# HABSat2_schematic1502.net
KiCad netlist of a schematic drawn in EasyEDA
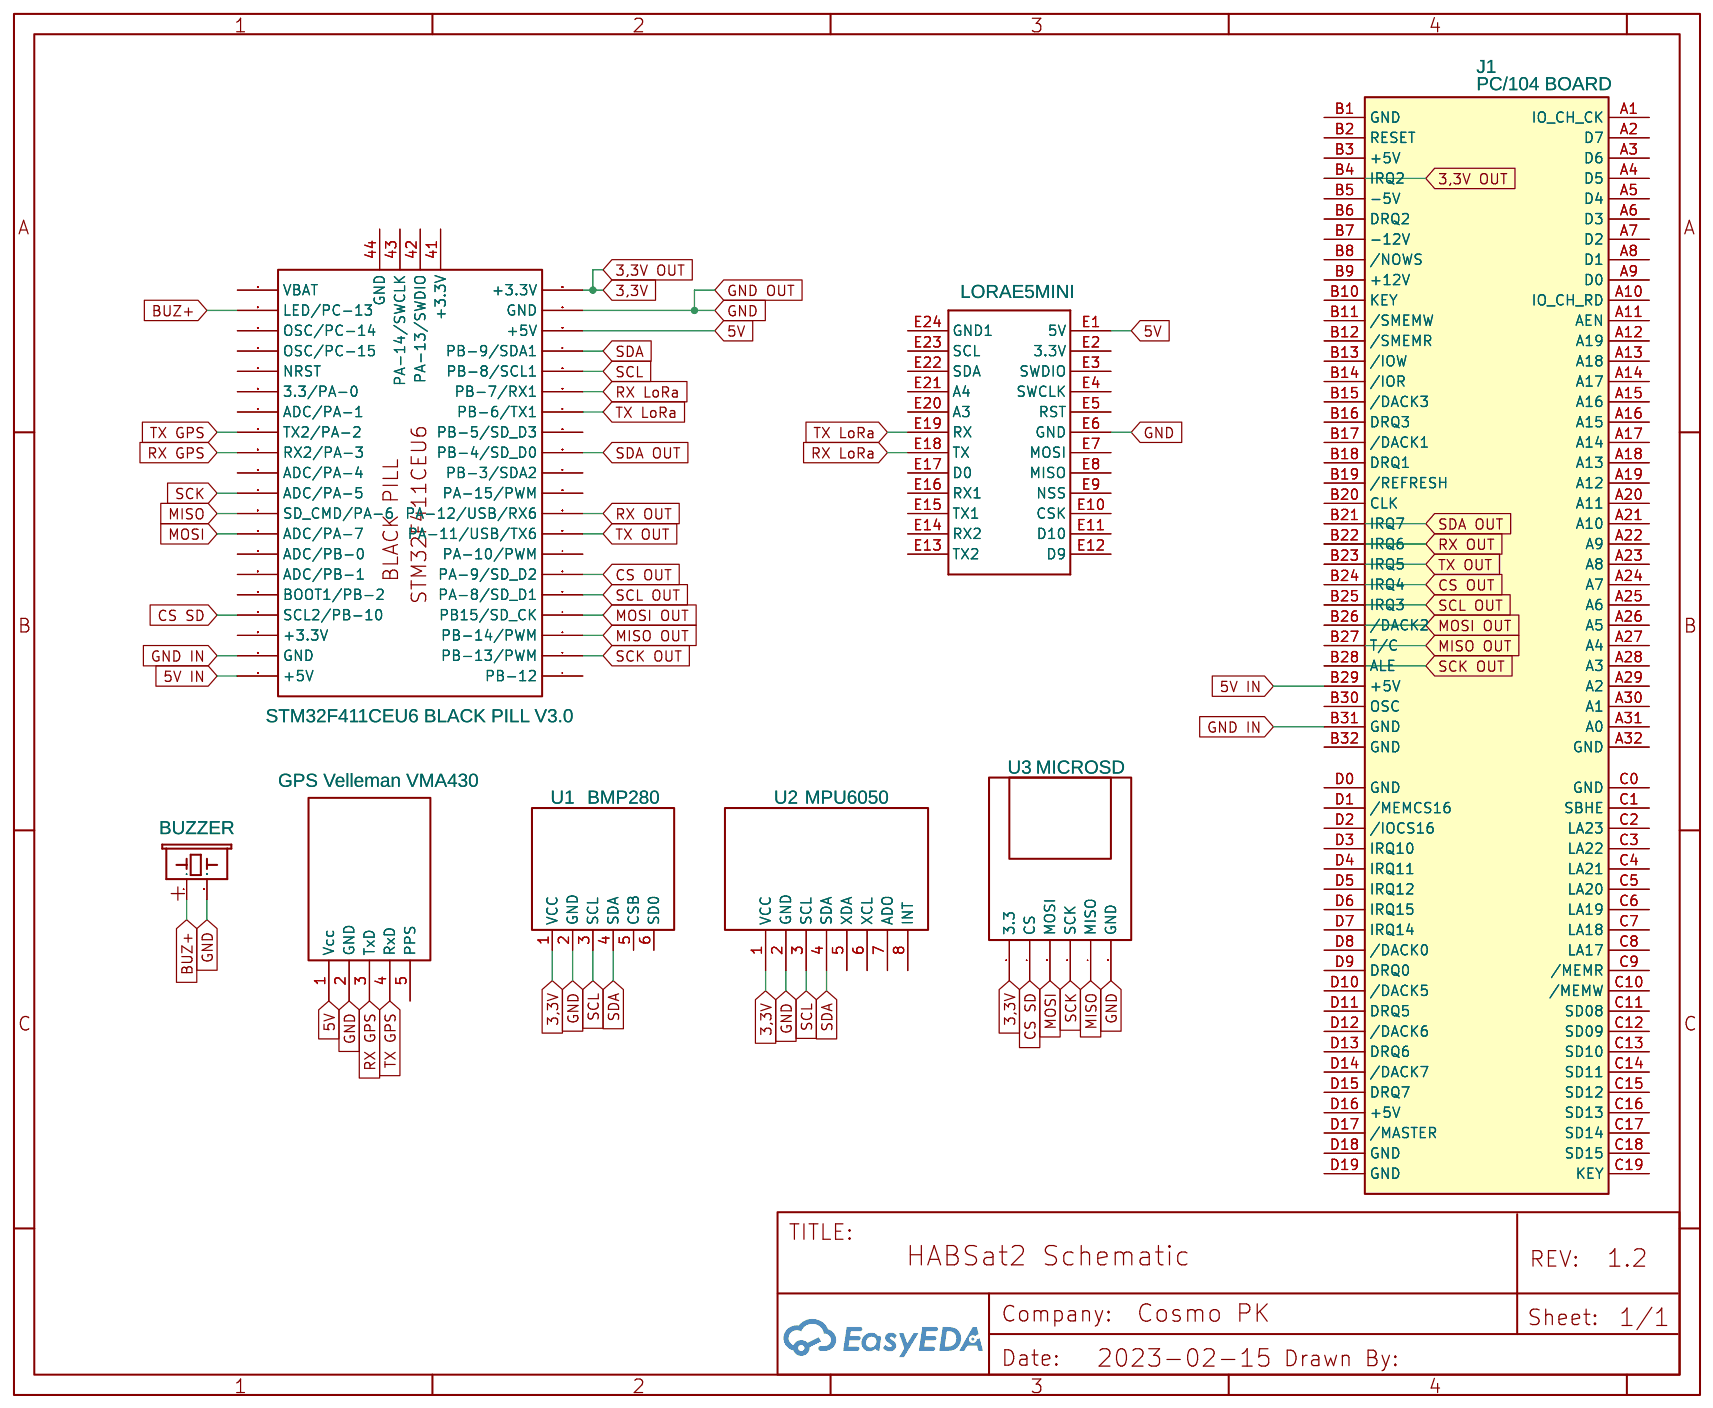
[diagram p0: schematic sheet]

(export (version "E")
  (design (tool "Eeschema 10.0.6"))
  (components
    (comp (ref "1") (value "LORAE5MINI") (libsource (lib "") (part "LORAE5MINI")))
    (comp (ref "J1") (value "PC/104 BOARD") (libsource (lib "") (part "PC/104 BOARD")))
    (comp (ref "SG1") (value "BUZZER") (libsource (lib "") (part "BUZZER KX-12MM")))
    (comp (ref "STM1")
      (value "STM32F411CEU6 BLACK PILL V3.0")
      (libsource (lib "") (part "STM32F411CEU6 BLACK PILL V3.0"))
    )
    (comp (ref "U1")
      (value "BMP280")
      (fields (field (name "BOM_Manufacturer Part") "GY-BMP280"))
      (libsource (lib "") (part "GY-BMP280"))
    )
    (comp (ref "U2") (value "MPU6050") (libsource (lib "") (part "MPU6050")))
    (comp (ref "U3") (value "MICROSD") (libsource (lib "") (part "MICROSD")))
    (comp (ref "VCC")
      (value "GPS Velleman VMA430")
      (fields (field (name "BOM_Manufacturer Part") "VMA430"))
      (libsource (lib "") (part "GPS Velleman VMA430"))
    )
  )
  (nets
    (net (code "1") (name "3,3V") (class "Default")
      (node (ref "J1") (pin "B4") (pinfunction "IRQ2_B4") (pintype "unspecified"))
      (node (ref "STM1") (pin "20") (pinfunction "+3.3V_20") (pintype "unspecified"))
      (node (ref "U1") (pin "1") (pinfunction "VCC_1") (pintype "unspecified"))
      (node (ref "U2") (pin "1") (pinfunction "VCC_1") (pintype "unspecified"))
      (node (ref "U3") (pin "5") (pinfunction "3.3_5") (pintype "unspecified"))
    )
    (net (code "2") (name "5V") (class "Default")
      (node (ref "1") (pin "E1") (pinfunction "5V_E1") (pintype "bidirectional"))
      (node (ref "STM1") (pin "18") (pinfunction "+5V_18") (pintype "unspecified"))
      (node (ref "VCC") (pin "1") (pinfunction "Vcc_1") (pintype "unspecified"))
    )
    (net (code "3") (name "5V IN") (class "Default")
      (node (ref "J1") (pin "B29") (pinfunction "+5V_B29") (pintype "bidirectional"))
      (node (ref "STM1") (pin "40") (pinfunction "+5V_40") (pintype "unspecified"))
    )
    (net (code "4") (name "BUZ+") (class "Default")
      (node (ref "SG1") (pin "1") (pinfunction "1_1") (pintype "unspecified"))
      (node (ref "STM1") (pin "22") (pinfunction "LED/PC-13_22") (pintype "unspecified"))
    )
    (net (code "5") (name "CS OUT") (class "Default")
      (node (ref "J1") (pin "B24") (pinfunction "IRQ4_B24") (pintype "unspecified"))
      (node (ref "STM1") (pin "6") (pinfunction "PA-9/SD_D2_6") (pintype "unspecified"))
    )
    (net (code "6") (name "CS SD") (class "Default")
      (node (ref "STM1") (pin "37") (pinfunction "SCL2/PB-10_37") (pintype "unspecified"))
      (node (ref "U3") (pin "1") (pinfunction "CS_1") (pintype "unspecified"))
    )
    (net (code "7") (name "GND") (class "Default")
      (node (ref "1") (pin "E6") (pinfunction "GND_E6") (pintype "bidirectional"))
      (node (ref "SG1") (pin "2") (pinfunction "2_2") (pintype "unspecified"))
      (node (ref "STM1") (pin "19") (pinfunction "GND_19") (pintype "unspecified"))
      (node (ref "U1") (pin "2") (pinfunction "GND_2") (pintype "unspecified"))
      (node (ref "U2") (pin "2") (pinfunction "GND_2") (pintype "unspecified"))
      (node (ref "U3") (pin "6") (pinfunction "GND_6") (pintype "unspecified"))
      (node (ref "VCC") (pin "2") (pinfunction "GND_2") (pintype "unspecified"))
    )
    (net (code "8") (name "GND IN") (class "Default")
      (node (ref "J1") (pin "B31") (pinfunction "GND_B31") (pintype "bidirectional"))
      (node (ref "STM1") (pin "39") (pinfunction "GND_39") (pintype "unspecified"))
    )
    (net (code "9") (name "MISO") (class "Default")
      (node (ref "STM1") (pin "32") (pinfunction "SD_CMD/PA-6_32") (pintype "unspecified"))
      (node (ref "U3") (pin "4") (pinfunction "MISO_4") (pintype "unspecified"))
    )
    (net (code "10") (name "MISO OUT") (class "Default")
      (node (ref "J1") (pin "B27") (pinfunction "T/C_B27") (pintype "unspecified"))
      (node (ref "STM1") (pin "3") (pinfunction "PB-14/PWM_3") (pintype "unspecified"))
    )
    (net (code "11") (name "MOSI") (class "Default")
      (node (ref "STM1") (pin "33") (pinfunction "ADC/PA-7_33") (pintype "unspecified"))
      (node (ref "U3") (pin "3") (pinfunction "MOSI_3") (pintype "unspecified"))
    )
    (net (code "12") (name "MOSI OUT") (class "Default")
      (node (ref "J1") (pin "B26") (pinfunction "/DACK2_B26") (pintype "unspecified"))
      (node (ref "STM1") (pin "4") (pinfunction "PB15/SD_CK_4") (pintype "unspecified"))
    )
    (net (code "13") (name "RX GPS") (class "Default")
      (node (ref "STM1") (pin "29") (pinfunction "RX2/PA-3_29") (pintype "unspecified"))
      (node (ref "VCC") (pin "3") (pinfunction "TxD_3") (pintype "unspecified"))
    )
    (net (code "14") (name "RX LoRa") (class "Default")
      (node (ref "1") (pin "E18") (pinfunction "TX_E18") (pintype "bidirectional"))
      (node (ref "STM1") (pin "15") (pinfunction "PB-7/RX1_15") (pintype "unspecified"))
    )
    (net (code "15") (name "RX OUT") (class "Default")
      (node (ref "J1") (pin "B22") (pinfunction "IRQ6_B22") (pintype "unspecified"))
      (node (ref "STM1") (pin "9") (pinfunction "PA-12/USB/RX6_9") (pintype "unspecified"))
    )
    (net (code "16") (name "SCK") (class "Default")
      (node (ref "STM1") (pin "31") (pinfunction "ADC/PA-5_31") (pintype "unspecified"))
      (node (ref "U3") (pin "2") (pinfunction "SCK_2") (pintype "unspecified"))
    )
    (net (code "17") (name "SCK OUT") (class "Default")
      (node (ref "J1") (pin "B28") (pinfunction "ALE_B28") (pintype "output"))
      (node (ref "STM1") (pin "2") (pinfunction "PB-13/PWM_2") (pintype "unspecified"))
    )
    (net (code "18") (name "SCL") (class "Default")
      (node (ref "STM1") (pin "16") (pinfunction "PB-8/SCL1_16") (pintype "unspecified"))
      (node (ref "U1") (pin "3") (pinfunction "SCL_3") (pintype "unspecified"))
      (node (ref "U2") (pin "3") (pinfunction "SCL_3") (pintype "unspecified"))
    )
    (net (code "19") (name "SCL OUT") (class "Default")
      (node (ref "J1") (pin "B25") (pinfunction "IRQ3_B25") (pintype "unspecified"))
      (node (ref "STM1") (pin "5") (pinfunction "PA-8/SD_D1_5") (pintype "unspecified"))
    )
    (net (code "20") (name "SDA") (class "Default")
      (node (ref "STM1") (pin "17") (pinfunction "PB-9/SDA1_17") (pintype "unspecified"))
      (node (ref "U1") (pin "4") (pinfunction "SDA_4") (pintype "unspecified"))
      (node (ref "U2") (pin "4") (pinfunction "SDA_4") (pintype "unspecified"))
    )
    (net (code "21") (name "SDA OUT") (class "Default")
      (node (ref "J1") (pin "B21") (pinfunction "IRQ7_B21") (pintype "unspecified"))
      (node (ref "STM1") (pin "12") (pinfunction "PB-4/SD_D0_12") (pintype "unspecified"))
    )
    (net (code "22") (name "TX GPS") (class "Default")
      (node (ref "STM1") (pin "28") (pinfunction "TX2/PA-2_28") (pintype "unspecified"))
      (node (ref "VCC") (pin "4") (pinfunction "RxD_4") (pintype "unspecified"))
    )
    (net (code "23") (name "TX LoRa") (class "Default")
      (node (ref "1") (pin "E19") (pinfunction "RX_E19") (pintype "bidirectional"))
      (node (ref "STM1") (pin "14") (pinfunction "PB-6/TX1_14") (pintype "unspecified"))
    )
    (net (code "24") (name "TX OUT") (class "Default")
      (node (ref "J1") (pin "B23") (pinfunction "IRQ5_B23") (pintype "unspecified"))
      (node (ref "STM1") (pin "8") (pinfunction "PA-11/USB/TX6_8") (pintype "unspecified"))
    )
    (net (code "25") (name "unconnected-(1-3.3V-PadE2)") (class "Default")
      (node (ref "1") (pin "E2") (pinfunction "3.3V_E2") (pintype "bidirectional"))
    )
    (net (code "26") (name "unconnected-(1-A3-PadE20)") (class "Default")
      (node (ref "1") (pin "E20") (pinfunction "A3_E20") (pintype "bidirectional"))
    )
    (net (code "27") (name "unconnected-(1-A4-PadE21)") (class "Default")
      (node (ref "1") (pin "E21") (pinfunction "A4_E21") (pintype "bidirectional"))
    )
    (net (code "28") (name "unconnected-(1-CSK-PadE10)") (class "Default")
      (node (ref "1") (pin "E10") (pinfunction "CSK_E10") (pintype "bidirectional"))
    )
    (net (code "29") (name "unconnected-(1-D0-PadE17)") (class "Default")
      (node (ref "1") (pin "E17") (pinfunction "D0_E17") (pintype "bidirectional"))
    )
    (net (code "30") (name "unconnected-(1-D9-PadE12)") (class "Default")
      (node (ref "1") (pin "E12") (pinfunction "D9_E12") (pintype "bidirectional"))
    )
    (net (code "31") (name "unconnected-(1-D10-PadE11)") (class "Default")
      (node (ref "1") (pin "E11") (pinfunction "D10_E11") (pintype "bidirectional"))
    )
    (net (code "32") (name "unconnected-(1-GND1-PadE24)") (class "Default")
      (node (ref "1") (pin "E24") (pinfunction "GND1_E24") (pintype "bidirectional"))
    )
    (net (code "33") (name "unconnected-(1-MISO-PadE8)") (class "Default")
      (node (ref "1") (pin "E8") (pinfunction "MISO_E8") (pintype "bidirectional"))
    )
    (net (code "34") (name "unconnected-(1-MOSI-PadE7)") (class "Default")
      (node (ref "1") (pin "E7") (pinfunction "MOSI_E7") (pintype "bidirectional"))
    )
    (net (code "35") (name "unconnected-(1-NSS-PadE9)") (class "Default")
      (node (ref "1") (pin "E9") (pinfunction "NSS_E9") (pintype "bidirectional"))
    )
    (net (code "36") (name "unconnected-(1-RST-PadE5)") (class "Default")
      (node (ref "1") (pin "E5") (pinfunction "RST_E5") (pintype "bidirectional"))
    )
    (net (code "37") (name "unconnected-(1-RX1-PadE16)") (class "Default")
      (node (ref "1") (pin "E16") (pinfunction "RX1_E16") (pintype "bidirectional"))
    )
    (net (code "38") (name "unconnected-(1-RX2-PadE14)") (class "Default")
      (node (ref "1") (pin "E14") (pinfunction "RX2_E14") (pintype "bidirectional"))
    )
    (net (code "39") (name "unconnected-(1-SCL-PadE23)") (class "Default")
      (node (ref "1") (pin "E23") (pinfunction "SCL_E23") (pintype "bidirectional"))
    )
    (net (code "40") (name "unconnected-(1-SDA-PadE22)") (class "Default")
      (node (ref "1") (pin "E22") (pinfunction "SDA_E22") (pintype "bidirectional"))
    )
    (net (code "41") (name "unconnected-(1-SWCLK-PadE4)") (class "Default")
      (node (ref "1") (pin "E4") (pinfunction "SWCLK_E4") (pintype "bidirectional"))
    )
    (net (code "42") (name "unconnected-(1-SWDIO-PadE3)") (class "Default")
      (node (ref "1") (pin "E3") (pinfunction "SWDIO_E3") (pintype "bidirectional"))
    )
    (net (code "43") (name "unconnected-(1-TX1-PadE15)") (class "Default")
      (node (ref "1") (pin "E15") (pinfunction "TX1_E15") (pintype "bidirectional"))
    )
    (net (code "44") (name "unconnected-(1-TX2-PadE13)") (class "Default")
      (node (ref "1") (pin "E13") (pinfunction "TX2_E13") (pintype "bidirectional"))
    )
    (net (code "45") (name "unconnected-(J1-+5V-PadB3)") (class "Default")
      (node (ref "J1") (pin "B3") (pinfunction "+5V_B3") (pintype "bidirectional"))
    )
    (net (code "46") (name "unconnected-(J1-+5V-PadD16)") (class "Default")
      (node (ref "J1") (pin "D16") (pinfunction "+5V_D16") (pintype "bidirectional"))
    )
    (net (code "47") (name "unconnected-(J1-+12V-PadB9)") (class "Default")
      (node (ref "J1") (pin "B9") (pinfunction "+12V_B9") (pintype "bidirectional"))
    )
    (net (code "48") (name "unconnected-(J1--5V-PadB5)") (class "Default")
      (node (ref "J1") (pin "B5") (pinfunction "-5V_B5") (pintype "bidirectional"))
    )
    (net (code "49") (name "unconnected-(J1--12V-PadB7)") (class "Default")
      (node (ref "J1") (pin "B7") (pinfunction "-12V_B7") (pintype "bidirectional"))
    )
    (net (code "50") (name "unconnected-(J1-A0-PadA31)") (class "Default")
      (node (ref "J1") (pin "A31") (pinfunction "A0_A31") (pintype "bidirectional"))
    )
    (net (code "51") (name "unconnected-(J1-A1-PadA30)") (class "Default")
      (node (ref "J1") (pin "A30") (pinfunction "A1_A30") (pintype "bidirectional"))
    )
    (net (code "52") (name "unconnected-(J1-A2-PadA29)") (class "Default")
      (node (ref "J1") (pin "A29") (pinfunction "A2_A29") (pintype "bidirectional"))
    )
    (net (code "53") (name "unconnected-(J1-A3-PadA28)") (class "Default")
      (node (ref "J1") (pin "A28") (pinfunction "A3_A28") (pintype "bidirectional"))
    )
    (net (code "54") (name "unconnected-(J1-A4-PadA27)") (class "Default")
      (node (ref "J1") (pin "A27") (pinfunction "A4_A27") (pintype "bidirectional"))
    )
    (net (code "55") (name "unconnected-(J1-A5-PadA26)") (class "Default")
      (node (ref "J1") (pin "A26") (pinfunction "A5_A26") (pintype "bidirectional"))
    )
    (net (code "56") (name "unconnected-(J1-A6-PadA25)") (class "Default")
      (node (ref "J1") (pin "A25") (pinfunction "A6_A25") (pintype "bidirectional"))
    )
    (net (code "57") (name "unconnected-(J1-A7-PadA24)") (class "Default")
      (node (ref "J1") (pin "A24") (pinfunction "A7_A24") (pintype "bidirectional"))
    )
    (net (code "58") (name "unconnected-(J1-A8-PadA23)") (class "Default")
      (node (ref "J1") (pin "A23") (pinfunction "A8_A23") (pintype "bidirectional"))
    )
    (net (code "59") (name "unconnected-(J1-A9-PadA22)") (class "Default")
      (node (ref "J1") (pin "A22") (pinfunction "A9_A22") (pintype "bidirectional"))
    )
    (net (code "60") (name "unconnected-(J1-A10-PadA21)") (class "Default")
      (node (ref "J1") (pin "A21") (pinfunction "A10_A21") (pintype "bidirectional"))
    )
    (net (code "61") (name "unconnected-(J1-A11-PadA20)") (class "Default")
      (node (ref "J1") (pin "A20") (pinfunction "A11_A20") (pintype "bidirectional"))
    )
    (net (code "62") (name "unconnected-(J1-A12-PadA19)") (class "Default")
      (node (ref "J1") (pin "A19") (pinfunction "A12_A19") (pintype "bidirectional"))
    )
    (net (code "63") (name "unconnected-(J1-A13-PadA18)") (class "Default")
      (node (ref "J1") (pin "A18") (pinfunction "A13_A18") (pintype "bidirectional"))
    )
    (net (code "64") (name "unconnected-(J1-A14-PadA17)") (class "Default")
      (node (ref "J1") (pin "A17") (pinfunction "A14_A17") (pintype "bidirectional"))
    )
    (net (code "65") (name "unconnected-(J1-A15-PadA16)") (class "Default")
      (node (ref "J1") (pin "A16") (pinfunction "A15_A16") (pintype "bidirectional"))
    )
    (net (code "66") (name "unconnected-(J1-A16-PadA15)") (class "Default")
      (node (ref "J1") (pin "A15") (pinfunction "A16_A15") (pintype "bidirectional"))
    )
    (net (code "67") (name "unconnected-(J1-A17-PadA14)") (class "Default")
      (node (ref "J1") (pin "A14") (pinfunction "A17_A14") (pintype "bidirectional"))
    )
    (net (code "68") (name "unconnected-(J1-A18-PadA13)") (class "Default")
      (node (ref "J1") (pin "A13") (pinfunction "A18_A13") (pintype "bidirectional"))
    )
    (net (code "69") (name "unconnected-(J1-A19-PadA12)") (class "Default")
      (node (ref "J1") (pin "A12") (pinfunction "A19_A12") (pintype "bidirectional"))
    )
    (net (code "70") (name "unconnected-(J1-AEN-PadA11)") (class "Default")
      (node (ref "J1") (pin "A11") (pinfunction "AEN_A11") (pintype "output"))
    )
    (net (code "71") (name "unconnected-(J1-CLK-PadB20)") (class "Default")
      (node (ref "J1") (pin "B20") (pinfunction "CLK_B20") (pintype "output"))
    )
    (net (code "72") (name "unconnected-(J1-D0-PadA9)") (class "Default")
      (node (ref "J1") (pin "A9") (pinfunction "D0_A9") (pintype "bidirectional"))
    )
    (net (code "73") (name "unconnected-(J1-D1-PadA8)") (class "Default")
      (node (ref "J1") (pin "A8") (pinfunction "D1_A8") (pintype "bidirectional"))
    )
    (net (code "74") (name "unconnected-(J1-D2-PadA7)") (class "Default")
      (node (ref "J1") (pin "A7") (pinfunction "D2_A7") (pintype "bidirectional"))
    )
    (net (code "75") (name "unconnected-(J1-D3-PadA6)") (class "Default")
      (node (ref "J1") (pin "A6") (pinfunction "D3_A6") (pintype "bidirectional"))
    )
    (net (code "76") (name "unconnected-(J1-D4-PadA5)") (class "Default")
      (node (ref "J1") (pin "A5") (pinfunction "D4_A5") (pintype "bidirectional"))
    )
    (net (code "77") (name "unconnected-(J1-D5-PadA4)") (class "Default")
      (node (ref "J1") (pin "A4") (pinfunction "D5_A4") (pintype "bidirectional"))
    )
    (net (code "78") (name "unconnected-(J1-D6-PadA3)") (class "Default")
      (node (ref "J1") (pin "A3") (pinfunction "D6_A3") (pintype "bidirectional"))
    )
    (net (code "79") (name "unconnected-(J1-D7-PadA2)") (class "Default")
      (node (ref "J1") (pin "A2") (pinfunction "D7_A2") (pintype "bidirectional"))
    )
    (net (code "80") (name "unconnected-(J1-DRQ0-PadD9)") (class "Default")
      (node (ref "J1") (pin "D9") (pinfunction "DRQ0_D9") (pintype "unspecified"))
    )
    (net (code "81") (name "unconnected-(J1-DRQ1-PadB18)") (class "Default")
      (node (ref "J1") (pin "B18") (pinfunction "DRQ1_B18") (pintype "unspecified"))
    )
    (net (code "82") (name "unconnected-(J1-DRQ2-PadB6)") (class "Default")
      (node (ref "J1") (pin "B6") (pinfunction "DRQ2_B6") (pintype "unspecified"))
    )
    (net (code "83") (name "unconnected-(J1-DRQ3-PadB16)") (class "Default")
      (node (ref "J1") (pin "B16") (pinfunction "DRQ3_B16") (pintype "unspecified"))
    )
    (net (code "84") (name "unconnected-(J1-DRQ5-PadD11)") (class "Default")
      (node (ref "J1") (pin "D11") (pinfunction "DRQ5_D11") (pintype "unspecified"))
    )
    (net (code "85") (name "unconnected-(J1-DRQ6-PadD13)") (class "Default")
      (node (ref "J1") (pin "D13") (pinfunction "DRQ6_D13") (pintype "unspecified"))
    )
    (net (code "86") (name "unconnected-(J1-DRQ7-PadD15)") (class "Default")
      (node (ref "J1") (pin "D15") (pinfunction "DRQ7_D15") (pintype "unspecified"))
    )
    (net (code "87") (name "unconnected-(J1-GND-PadA32)") (class "Default")
      (node (ref "J1") (pin "A32") (pinfunction "GND_A32") (pintype "bidirectional"))
    )
    (net (code "88") (name "unconnected-(J1-GND-PadB1)") (class "Default")
      (node (ref "J1") (pin "B1") (pinfunction "GND_B1") (pintype "bidirectional"))
    )
    (net (code "89") (name "unconnected-(J1-GND-PadB32)") (class "Default")
      (node (ref "J1") (pin "B32") (pinfunction "GND_B32") (pintype "bidirectional"))
    )
    (net (code "90") (name "unconnected-(J1-GND-PadC0)") (class "Default")
      (node (ref "J1") (pin "C0") (pinfunction "GND_C0") (pintype "unspecified"))
    )
    (net (code "91") (name "unconnected-(J1-GND-PadD0)") (class "Default")
      (node (ref "J1") (pin "D0") (pinfunction "GND_D0") (pintype "unspecified"))
    )
    (net (code "92") (name "unconnected-(J1-GND-PadD18)") (class "Default")
      (node (ref "J1") (pin "D18") (pinfunction "GND_D18") (pintype "bidirectional"))
    )
    (net (code "93") (name "unconnected-(J1-GND-PadD19)") (class "Default")
      (node (ref "J1") (pin "D19") (pinfunction "GND_D19") (pintype "bidirectional"))
    )
    (net (code "94") (name "unconnected-(J1-IO_CH_CK-PadA1)") (class "Default")
      (node (ref "J1") (pin "A1") (pinfunction "IO_CH_CK_A1") (pintype "unspecified"))
    )
    (net (code "95") (name "unconnected-(J1-IO_CH_RD-PadA10)") (class "Default")
      (node (ref "J1") (pin "A10") (pinfunction "IO_CH_RD_A10") (pintype "unspecified"))
    )
    (net (code "96") (name "unconnected-(J1-IRQ10-PadD3)") (class "Default")
      (node (ref "J1") (pin "D3") (pinfunction "IRQ10_D3") (pintype "unspecified"))
    )
    (net (code "97") (name "unconnected-(J1-IRQ11-PadD4)") (class "Default")
      (node (ref "J1") (pin "D4") (pinfunction "IRQ11_D4") (pintype "unspecified"))
    )
    (net (code "98") (name "unconnected-(J1-IRQ12-PadD5)") (class "Default")
      (node (ref "J1") (pin "D5") (pinfunction "IRQ12_D5") (pintype "unspecified"))
    )
    (net (code "99") (name "unconnected-(J1-IRQ14-PadD7)") (class "Default")
      (node (ref "J1") (pin "D7") (pinfunction "IRQ14_D7") (pintype "unspecified"))
    )
    (net (code "100") (name "unconnected-(J1-IRQ15-PadD6)") (class "Default")
      (node (ref "J1") (pin "D6") (pinfunction "IRQ15_D6") (pintype "unspecified"))
    )
    (net (code "101") (name "unconnected-(J1-KEY-PadB10)") (class "Default")
      (node (ref "J1") (pin "B10") (pinfunction "KEY_B10") (pintype "bidirectional"))
    )
    (net (code "102") (name "unconnected-(J1-KEY-PadC19)") (class "Default")
      (node (ref "J1") (pin "C19") (pinfunction "KEY_C19") (pintype "bidirectional"))
    )
    (net (code "103") (name "unconnected-(J1-LA17-PadC8)") (class "Default")
      (node (ref "J1") (pin "C8") (pinfunction "LA17_C8") (pintype "unspecified"))
    )
    (net (code "104") (name "unconnected-(J1-LA18-PadC7)") (class "Default")
      (node (ref "J1") (pin "C7") (pinfunction "LA18_C7") (pintype "unspecified"))
    )
    (net (code "105") (name "unconnected-(J1-LA19-PadC6)") (class "Default")
      (node (ref "J1") (pin "C6") (pinfunction "LA19_C6") (pintype "unspecified"))
    )
    (net (code "106") (name "unconnected-(J1-LA20-PadC5)") (class "Default")
      (node (ref "J1") (pin "C5") (pinfunction "LA20_C5") (pintype "unspecified"))
    )
    (net (code "107") (name "unconnected-(J1-LA21-PadC4)") (class "Default")
      (node (ref "J1") (pin "C4") (pinfunction "LA21_C4") (pintype "unspecified"))
    )
    (net (code "108") (name "unconnected-(J1-LA22-PadC3)") (class "Default")
      (node (ref "J1") (pin "C3") (pinfunction "LA22_C3") (pintype "unspecified"))
    )
    (net (code "109") (name "unconnected-(J1-LA23-PadC2)") (class "Default")
      (node (ref "J1") (pin "C2") (pinfunction "LA23_C2") (pintype "unspecified"))
    )
    (net (code "110") (name "unconnected-(J1-OSC-PadB30)") (class "Default")
      (node (ref "J1") (pin "B30") (pinfunction "OSC_B30") (pintype "output"))
    )
    (net (code "111") (name "unconnected-(J1-RESET-PadB2)") (class "Default")
      (node (ref "J1") (pin "B2") (pinfunction "RESET_B2") (pintype "output"))
    )
    (net (code "112") (name "unconnected-(J1-SBHE-PadC1)") (class "Default")
      (node (ref "J1") (pin "C1") (pinfunction "SBHE_C1") (pintype "unspecified"))
    )
    (net (code "113") (name "unconnected-(J1-SD08-PadC11)") (class "Default")
      (node (ref "J1") (pin "C11") (pinfunction "SD08_C11") (pintype "bidirectional"))
    )
    (net (code "114") (name "unconnected-(J1-SD09-PadC12)") (class "Default")
      (node (ref "J1") (pin "C12") (pinfunction "SD09_C12") (pintype "bidirectional"))
    )
    (net (code "115") (name "unconnected-(J1-SD10-PadC13)") (class "Default")
      (node (ref "J1") (pin "C13") (pinfunction "SD10_C13") (pintype "bidirectional"))
    )
    (net (code "116") (name "unconnected-(J1-SD11-PadC14)") (class "Default")
      (node (ref "J1") (pin "C14") (pinfunction "SD11_C14") (pintype "bidirectional"))
    )
    (net (code "117") (name "unconnected-(J1-SD12-PadC15)") (class "Default")
      (node (ref "J1") (pin "C15") (pinfunction "SD12_C15") (pintype "bidirectional"))
    )
    (net (code "118") (name "unconnected-(J1-SD13-PadC16)") (class "Default")
      (node (ref "J1") (pin "C16") (pinfunction "SD13_C16") (pintype "bidirectional"))
    )
    (net (code "119") (name "unconnected-(J1-SD14-PadC17)") (class "Default")
      (node (ref "J1") (pin "C17") (pinfunction "SD14_C17") (pintype "bidirectional"))
    )
    (net (code "120") (name "unconnected-(J1-SD15-PadC18)") (class "Default")
      (node (ref "J1") (pin "C18") (pinfunction "SD15_C18") (pintype "bidirectional"))
    )
    (net (code "121") (name "unconnected-(J1-{slash}DACK0-PadD8)") (class "Default")
      (node (ref "J1") (pin "D8") (pinfunction "/DACK0_D8") (pintype "output"))
    )
    (net (code "122") (name "unconnected-(J1-{slash}DACK1-PadB17)") (class "Default")
      (node (ref "J1") (pin "B17") (pinfunction "/DACK1_B17") (pintype "unspecified"))
    )
    (net (code "123") (name "unconnected-(J1-{slash}DACK3-PadB15)") (class "Default")
      (node (ref "J1") (pin "B15") (pinfunction "/DACK3_B15") (pintype "unspecified"))
    )
    (net (code "124") (name "unconnected-(J1-{slash}DACK5-PadD10)") (class "Default")
      (node (ref "J1") (pin "D10") (pinfunction "/DACK5_D10") (pintype "output"))
    )
    (net (code "125") (name "unconnected-(J1-{slash}DACK6-PadD12)") (class "Default")
      (node (ref "J1") (pin "D12") (pinfunction "/DACK6_D12") (pintype "output"))
    )
    (net (code "126") (name "unconnected-(J1-{slash}DACK7-PadD14)") (class "Default")
      (node (ref "J1") (pin "D14") (pinfunction "/DACK7_D14") (pintype "output"))
    )
    (net (code "127") (name "unconnected-(J1-{slash}IOCS16-PadD2)") (class "Default")
      (node (ref "J1") (pin "D2") (pinfunction "/IOCS16_D2") (pintype "unspecified"))
    )
    (net (code "128") (name "unconnected-(J1-{slash}IOR-PadB14)") (class "Default")
      (node (ref "J1") (pin "B14") (pinfunction "/IOR_B14") (pintype "output"))
    )
    (net (code "129") (name "unconnected-(J1-{slash}IOW-PadB13)") (class "Default")
      (node (ref "J1") (pin "B13") (pinfunction "/IOW_B13") (pintype "output"))
    )
    (net (code "130") (name "unconnected-(J1-{slash}MASTER-PadD17)") (class "Default")
      (node (ref "J1") (pin "D17") (pinfunction "/MASTER_D17") (pintype "unspecified"))
    )
    (net (code "131") (name "unconnected-(J1-{slash}MEMCS16-PadD1)") (class "Default")
      (node (ref "J1") (pin "D1") (pinfunction "/MEMCS16_D1") (pintype "unspecified"))
    )
    (net (code "132") (name "unconnected-(J1-{slash}MEMR-PadC9)") (class "Default")
      (node (ref "J1") (pin "C9") (pinfunction "/MEMR_C9") (pintype "output"))
    )
    (net (code "133") (name "unconnected-(J1-{slash}MEMW-PadC10)") (class "Default")
      (node (ref "J1") (pin "C10") (pinfunction "/MEMW_C10") (pintype "output"))
    )
    (net (code "134") (name "unconnected-(J1-{slash}NOWS-PadB8)") (class "Default")
      (node (ref "J1") (pin "B8") (pinfunction "/NOWS_B8") (pintype "unspecified"))
    )
    (net (code "135") (name "unconnected-(J1-{slash}REFRESH-PadB19)") (class "Default")
      (node (ref "J1") (pin "B19") (pinfunction "/REFRESH_B19") (pintype "unspecified"))
    )
    (net (code "136") (name "unconnected-(J1-{slash}SMEMR-PadB12)") (class "Default")
      (node (ref "J1") (pin "B12") (pinfunction "/SMEMR_B12") (pintype "output"))
    )
    (net (code "137") (name "unconnected-(J1-{slash}SMEMW-PadB11)") (class "Default")
      (node (ref "J1") (pin "B11") (pinfunction "/SMEMW_B11") (pintype "output"))
    )
    (net (code "138") (name "unconnected-(STM1-+3.3V-Pad38)") (class "Default")
      (node (ref "STM1") (pin "38") (pinfunction "+3.3V_38") (pintype "unspecified"))
    )
    (net (code "139") (name "unconnected-(STM1-+3.3V-Pad41)") (class "Default")
      (node (ref "STM1") (pin "41") (pinfunction "+3.3V_41") (pintype "unspecified"))
    )
    (net (code "140") (name "unconnected-(STM1-3.3{slash}PA-0-Pad26)") (class "Default")
      (node (ref "STM1") (pin "26") (pinfunction "3.3/PA-0_26") (pintype "unspecified"))
    )
    (net (code "141") (name "unconnected-(STM1-ADC{slash}PA-1-Pad27)") (class "Default")
      (node (ref "STM1") (pin "27") (pinfunction "ADC/PA-1_27") (pintype "unspecified"))
    )
    (net (code "142") (name "unconnected-(STM1-ADC{slash}PA-4-Pad30)") (class "Default")
      (node (ref "STM1") (pin "30") (pinfunction "ADC/PA-4_30") (pintype "unspecified"))
    )
    (net (code "143") (name "unconnected-(STM1-ADC{slash}PB-0-Pad34)") (class "Default")
      (node (ref "STM1") (pin "34") (pinfunction "ADC/PB-0_34") (pintype "unspecified"))
    )
    (net (code "144") (name "unconnected-(STM1-ADC{slash}PB-1-Pad35)") (class "Default")
      (node (ref "STM1") (pin "35") (pinfunction "ADC/PB-1_35") (pintype "unspecified"))
    )
    (net (code "145") (name "unconnected-(STM1-BOOT1{slash}PB-2-Pad36)") (class "Default")
      (node (ref "STM1") (pin "36") (pinfunction "BOOT1/PB-2_36") (pintype "unspecified"))
    )
    (net (code "146") (name "unconnected-(STM1-GND-Pad44)") (class "Default")
      (node (ref "STM1") (pin "44") (pinfunction "GND_44") (pintype "unspecified"))
    )
    (net (code "147") (name "unconnected-(STM1-NRST-Pad25)") (class "Default")
      (node (ref "STM1") (pin "25") (pinfunction "NRST_25") (pintype "unspecified"))
    )
    (net (code "148") (name "unconnected-(STM1-OSC{slash}PC-14-Pad23)") (class "Default")
      (node (ref "STM1") (pin "23") (pinfunction "OSC/PC-14_23") (pintype "unspecified"))
    )
    (net (code "149") (name "unconnected-(STM1-OSC{slash}PC-15-Pad24)") (class "Default")
      (node (ref "STM1") (pin "24") (pinfunction "OSC/PC-15_24") (pintype "unspecified"))
    )
    (net (code "150") (name "unconnected-(STM1-PA-10{slash}PWM-Pad7)") (class "Default")
      (node (ref "STM1") (pin "7") (pinfunction "PA-10/PWM_7") (pintype "unspecified"))
    )
    (net (code "151") (name "unconnected-(STM1-PA-13{slash}SWDIO-Pad42)") (class "Default")
      (node (ref "STM1") (pin "42") (pinfunction "PA-13/SWDIO_42") (pintype "unspecified"))
    )
    (net (code "152") (name "unconnected-(STM1-PA-14{slash}SWCLK-Pad43)") (class "Default")
      (node (ref "STM1") (pin "43") (pinfunction "PA-14/SWCLK_43") (pintype "unspecified"))
    )
    (net (code "153") (name "unconnected-(STM1-PA-15{slash}PWM-Pad10)") (class "Default")
      (node (ref "STM1") (pin "10") (pinfunction "PA-15/PWM_10") (pintype "unspecified"))
    )
    (net (code "154") (name "unconnected-(STM1-PB-3{slash}SDA2-Pad11)") (class "Default")
      (node (ref "STM1") (pin "11") (pinfunction "PB-3/SDA2_11") (pintype "unspecified"))
    )
    (net (code "155") (name "unconnected-(STM1-PB-5{slash}SD_D3-Pad13)") (class "Default")
      (node (ref "STM1") (pin "13") (pinfunction "PB-5/SD_D3_13") (pintype "unspecified"))
    )
    (net (code "156") (name "unconnected-(STM1-PB-12-Pad1)") (class "Default")
      (node (ref "STM1") (pin "1") (pinfunction "PB-12_1") (pintype "unspecified"))
    )
    (net (code "157") (name "unconnected-(STM1-VBAT-Pad21)") (class "Default")
      (node (ref "STM1") (pin "21") (pinfunction "VBAT_21") (pintype "unspecified"))
    )
    (net (code "158") (name "unconnected-(U1-CSB-Pad5)") (class "Default")
      (node (ref "U1") (pin "5") (pinfunction "CSB_5") (pintype "unspecified"))
    )
    (net (code "159") (name "unconnected-(U1-SD0-Pad6)") (class "Default")
      (node (ref "U1") (pin "6") (pinfunction "SD0_6") (pintype "unspecified"))
    )
    (net (code "160") (name "unconnected-(U2-ADO-Pad7)") (class "Default")
      (node (ref "U2") (pin "7") (pinfunction "ADO_7") (pintype "unspecified"))
    )
    (net (code "161") (name "unconnected-(U2-INT-Pad8)") (class "Default")
      (node (ref "U2") (pin "8") (pinfunction "INT_8") (pintype "unspecified"))
    )
    (net (code "162") (name "unconnected-(U2-XCL-Pad6)") (class "Default")
      (node (ref "U2") (pin "6") (pinfunction "XCL_6") (pintype "unspecified"))
    )
    (net (code "163") (name "unconnected-(U2-XDA-Pad5)") (class "Default")
      (node (ref "U2") (pin "5") (pinfunction "XDA_5") (pintype "unspecified"))
    )
    (net (code "164") (name "unconnected-(VCC-PPS-Pad5)") (class "Default")
      (node (ref "VCC") (pin "5") (pinfunction "PPS_5") (pintype "unspecified"))
    )
  )
)
